# KI_Bus.net
KiCad netlist of a schematic drawn in Altium Designer
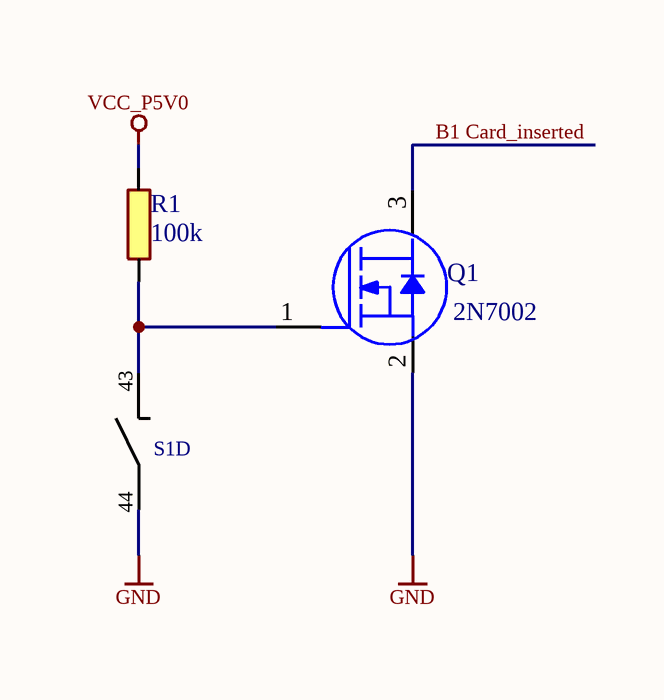
[diagram p0: KI_Bus.SchDoc]

(export (version "E")
  (design (tool "Eeschema 10.0.6"))
  (components
    (comp (ref "Q1")
      (value "2N7002")
      (footprint "SOT23-3_N")
      (description "N-Channel MOSFET 300mA")
      (libsource (lib "OVLib") (part "MOSFET_N_GSD"))
    )
    (comp (ref "R1")
      (value "100k")
      (footprint "RESC0603(1608)_N")
      (description "0.1W 1% Thick film resistor")
      (libsource (lib "OVLib") (part "Resistor2"))
    )
    (comp (ref "S1")
      (value "Automasjonsbryter")
      (description "Kraftig")
      (libsource (lib "OVLib") (part "AutomationSwitch"))
    )
  )
  (nets
    (net (code "1") (name "/B1 Card_inserted") (class "Default")
      (node (ref "Q1") (pin "3") (pinfunction "Drain_3") (pintype "passive"))
    )
    (net (code "2") (name "GND") (class "Default")
      (node (ref "Q1") (pin "2") (pinfunction "Source_2") (pintype "passive"))
      (node (ref "S1") (pin "44") (pinfunction "44_44") (pintype "passive"))
    )
    (net (code "3") (name "Net-(Q1-Gate)") (class "Default")
      (node (ref "Q1") (pin "1") (pinfunction "Gate_1") (pintype "passive"))
      (node (ref "R1") (pin "1") (pinfunction "1_1") (pintype "passive"))
      (node (ref "S1") (pin "43") (pinfunction "43_43") (pintype "passive"))
    )
    (net (code "4") (name "VCC_P5V0") (class "Default")
      (node (ref "R1") (pin "2") (pinfunction "2_2") (pintype "passive"))
    )
  )
)
